# PCB_2.net
KiCad netlist of a schematic drawn in EAGLE
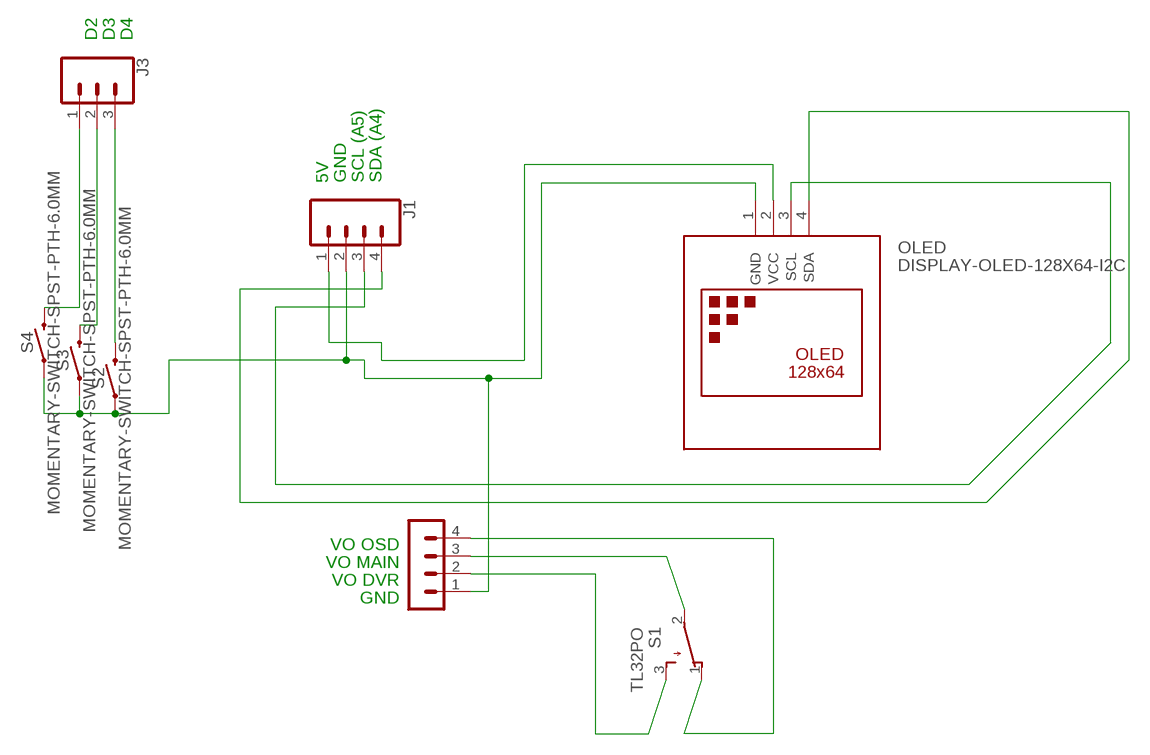
[diagram p0: schematic, sheet 1]

(export (version "E")
  (design (tool "Eeschema 10.0.6"))
  (components
    (comp (ref "IO3")
      (value "MA04-1")
      (footprint "eagle-import:MA04-1")
      (libsource (lib "eagle-import") (part "MA04-1"))
    )
    (comp (ref "J1")
      (value "CONN_04")
      (footprint "eagle-import:1X04")
      (libsource (lib "eagle-import") (part "CONN_04"))
    )
    (comp (ref "J3")
      (value "CONN_03")
      (footprint "eagle-import:1X03")
      (libsource (lib "eagle-import") (part "CONN_03"))
    )
    (comp (ref "OLED")
      (value "DISPLAY-OLED-128X64-I2C")
      (footprint "eagle-import:DISPLAY-OLED-128X64-I2C")
      (libsource (lib "eagle-import") (part "DISPLAY-OLED-128X64-I2C"))
    )
    (comp (ref "S1")
      (value "TL32PO")
      (footprint "eagle-import:TL3XPO")
      (libsource (lib "eagle-import") (part "TL32PO"))
    )
    (comp (ref "S2")
      (value "MOMENTARY-SWITCH-SPST-PTH-6.0MM")
      (footprint "eagle-import:TACTILE_SWITCH_PTH_6.0MM")
      (libsource (lib "eagle-import") (part "MOMENTARY-SWITCH-SPST-PTH-6.0MM"))
    )
    (comp (ref "S3")
      (value "MOMENTARY-SWITCH-SPST-PTH-6.0MM")
      (footprint "eagle-import:TACTILE_SWITCH_PTH_6.0MM")
      (libsource (lib "eagle-import") (part "MOMENTARY-SWITCH-SPST-PTH-6.0MM"))
    )
    (comp (ref "S4")
      (value "MOMENTARY-SWITCH-SPST-PTH-6.0MM")
      (footprint "eagle-import:TACTILE_SWITCH_PTH_6.0MM")
      (libsource (lib "eagle-import") (part "MOMENTARY-SWITCH-SPST-PTH-6.0MM"))
    )
  )
  (nets
    (net (code "1") (name "Net-(OLED-GND)") (class "Default")
      (node (ref "IO3") (pin "1") (pinfunction "1_1") (pintype "passive"))
      (node (ref "J1") (pin "2") (pinfunction "2_2") (pintype "passive"))
      (node (ref "OLED") (pin "1") (pinfunction "GND_1") (pintype "power_in"))
      (node (ref "S2") (pin "1") (pinfunction "1_1") (pintype "passive"))
      (node (ref "S3") (pin "1") (pinfunction "1_1") (pintype "passive"))
      (node (ref "S4") (pin "1") (pinfunction "1_1") (pintype "passive"))
    )
    (net (code "2") (name "Net-(OLED-SCL)") (class "Default")
      (node (ref "J1") (pin "3") (pinfunction "3_3") (pintype "passive"))
      (node (ref "OLED") (pin "3") (pinfunction "SCL_3") (pintype "bidirectional"))
    )
    (net (code "3") (name "Net-(OLED-SDA)") (class "Default")
      (node (ref "J1") (pin "4") (pinfunction "4_4") (pintype "passive"))
      (node (ref "OLED") (pin "4") (pinfunction "SDA_4") (pintype "bidirectional"))
    )
    (net (code "4") (name "Net-(OLED-VCC)") (class "Default")
      (node (ref "J1") (pin "1") (pinfunction "1_1") (pintype "passive"))
      (node (ref "OLED") (pin "2") (pinfunction "VCC_2") (pintype "power_in"))
    )
    (net (code "5") (name "Net-(S1-O)") (class "Default")
      (node (ref "IO3") (pin "4") (pinfunction "4_4") (pintype "passive"))
      (node (ref "S1") (pin "1") (pinfunction "O_1") (pintype "passive"))
    )
    (net (code "6") (name "Net-(S1-P)") (class "Default")
      (node (ref "IO3") (pin "3") (pinfunction "3_3") (pintype "passive"))
      (node (ref "S1") (pin "2") (pinfunction "P_2") (pintype "passive"))
    )
    (net (code "7") (name "Net-(S1-S)") (class "Default")
      (node (ref "IO3") (pin "2") (pinfunction "2_2") (pintype "passive"))
      (node (ref "S1") (pin "3") (pinfunction "S_3") (pintype "passive"))
    )
    (net (code "8") (name "Net-(S2-2)") (class "Default")
      (node (ref "J3") (pin "3") (pinfunction "3_3") (pintype "passive"))
      (node (ref "S2") (pin "3") (pinfunction "2_3") (pintype "passive"))
    )
    (net (code "9") (name "Net-(S3-2)") (class "Default")
      (node (ref "J3") (pin "2") (pinfunction "2_2") (pintype "passive"))
      (node (ref "S3") (pin "3") (pinfunction "2_3") (pintype "passive"))
    )
    (net (code "10") (name "Net-(S4-2)") (class "Default")
      (node (ref "J3") (pin "1") (pinfunction "1_1") (pintype "passive"))
      (node (ref "S4") (pin "3") (pinfunction "2_3") (pintype "passive"))
    )
  )
)
